# gdo_v7.net
KiCad netlist of a schematic drawn in EAGLE
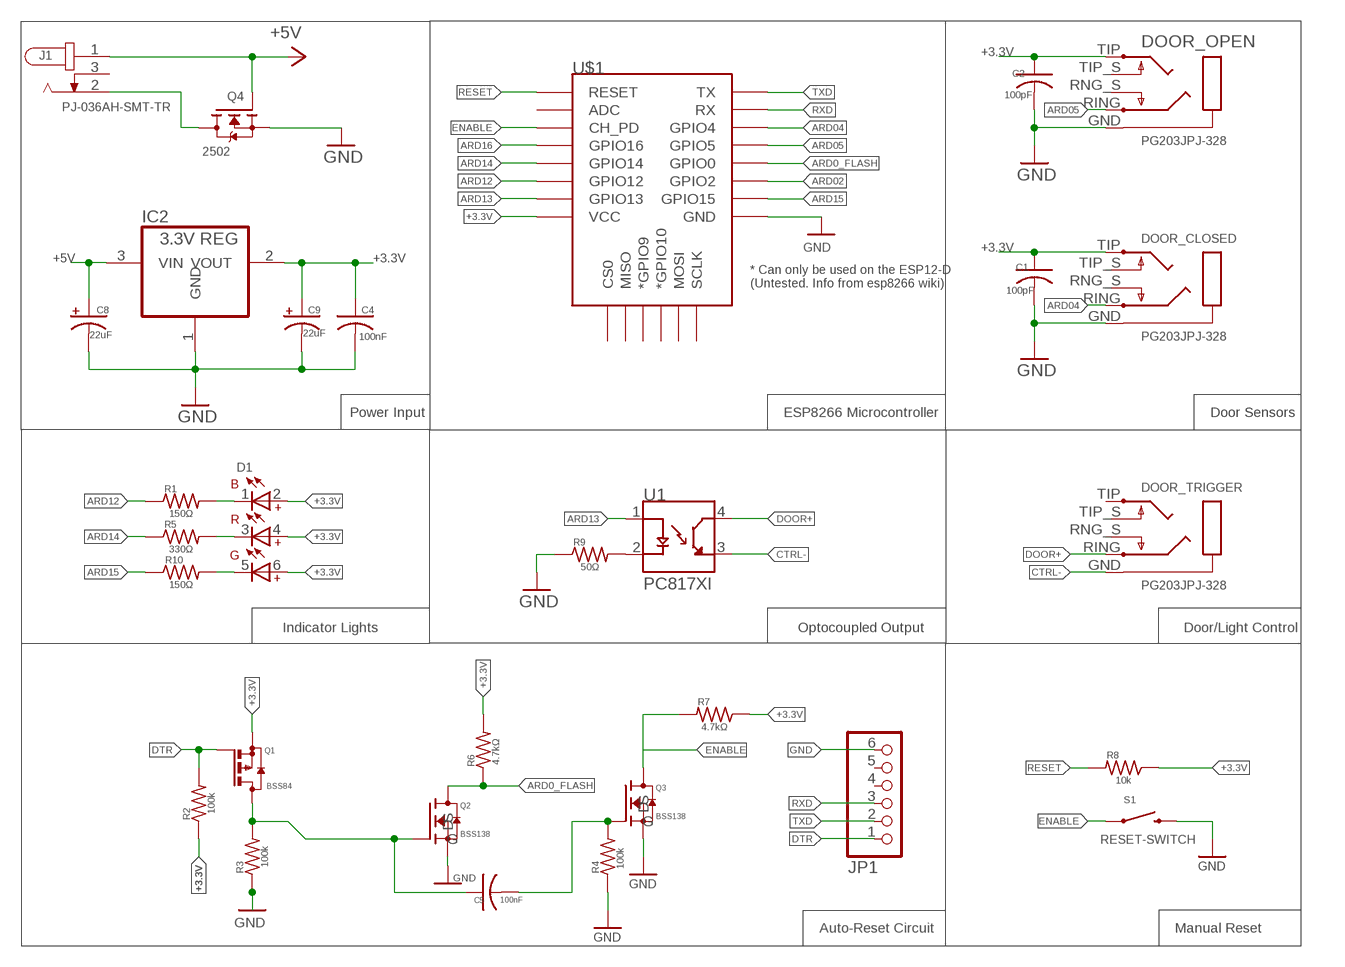
[diagram p0: schematic, sheet 1]

(export (version "E")
  (design (tool "Eeschema 10.0.6"))
  (components
    (comp (ref "C1")
      (value "100pF")
      (footprint "eagle-import:C0805")
      (libsource (lib "eagle-import") (part "C-USC0805"))
    )
    (comp (ref "C2")
      (value "100pF")
      (footprint "eagle-import:C0805")
      (libsource (lib "eagle-import") (part "C-USC0805"))
    )
    (comp (ref "C4")
      (value "100nF")
      (footprint "eagle-import:C0805")
      (libsource (lib "eagle-import") (part "C-USC0805"))
    )
    (comp (ref "C5")
      (value "100nF")
      (footprint "eagle-import:C0805")
      (libsource (lib "eagle-import") (part "C-USC0805"))
    )
    (comp (ref "C8")
      (value "22uF")
      (footprint "eagle-import:EIA3216")
      (libsource (lib "eagle-import") (part "10UF-TANT"))
    )
    (comp (ref "C9")
      (value "22uF")
      (footprint "eagle-import:EIA3216")
      (libsource (lib "eagle-import") (part "10UF-TANT"))
    )
    (comp (ref "D1")
      (value "WL-SFTW_5050_PLCC6_150505M173300")
      (footprint "eagle-import:WL-SFTW_5050_PLCC6")
      (libsource (lib "eagle-import") (part "WL-SFTW_5050_PLCC6_150505M173300"))
    )
    (comp (ref "DOOR_CLOSED")
      (value "PG203JPJ-328")
      (footprint "eagle-import:PG203J")
      (libsource (lib "eagle-import") (part "PG203JPJ-328"))
    )
    (comp (ref "DOOR_OPEN")
      (value "PG203JPJ-328")
      (footprint "eagle-import:PG203J")
      (libsource (lib "eagle-import") (part "PG203JPJ-328"))
    )
    (comp (ref "DOOR_TRIGGER")
      (value "PG203JPJ-328")
      (footprint "eagle-import:PG203J")
      (libsource (lib "eagle-import") (part "PG203JPJ-328"))
    )
    (comp (ref "IC2")
      (value "3.3V REG")
      (footprint "eagle-import:SOT223")
      (fields (field (name "MPN") "REG1117"))
      (libsource (lib "eagle-import") (part "REG1117"))
    )
    (comp (ref "J1")
      (value "PJ-036AH-SMT-TR")
      (footprint "eagle-import:CUI_PJ-036AH-SMT-TR")
      (fields (field (name "MF") "CUI Devices"))
      (libsource (lib "eagle-import") (part "PJ-036AH-SMT-TR"))
    )
    (comp (ref "JP1")
      (value "PINHD-1X6")
      (footprint "eagle-import:1X06")
      (libsource (lib "eagle-import") (part "PINHD-1X6"))
    )
    (comp (ref "Q1")
      (value "BSS84")
      (footprint "eagle-import:SOT23")
      (libsource (lib "eagle-import") (part "BSS84"))
    )
    (comp (ref "Q2")
      (value "BSS138")
      (footprint "eagle-import:BSS138")
      (libsource (lib "eagle-import") (part "BSS138"))
    )
    (comp (ref "Q3")
      (value "BSS138")
      (footprint "eagle-import:BSS138")
      (libsource (lib "eagle-import") (part "BSS138"))
    )
    (comp (ref "Q4")
      (value "2502")
      (footprint "eagle-import:SOT23")
      (fields (field (name "MF") "Fairchild") (field (name "MPN") "BSS138"))
      (libsource (lib "eagle-import") (part "bss138_10_BSS138"))
    )
    (comp (ref "R1")
      (value "150Ω")
      (footprint "eagle-import:R0805")
      (libsource (lib "eagle-import") (part "R-US_R0805"))
    )
    (comp (ref "R2")
      (value "100k")
      (footprint "eagle-import:R0805")
      (libsource (lib "eagle-import") (part "R-US_R0805"))
    )
    (comp (ref "R3")
      (value "100k")
      (footprint "eagle-import:R0805")
      (libsource (lib "eagle-import") (part "R-US_R0805"))
    )
    (comp (ref "R4")
      (value "100k")
      (footprint "eagle-import:R0805")
      (libsource (lib "eagle-import") (part "R-US_R0805"))
    )
    (comp (ref "R5")
      (value "330Ω")
      (footprint "eagle-import:R0805")
      (libsource (lib "eagle-import") (part "R-US_R0805"))
    )
    (comp (ref "R6")
      (value "4.7kΩ")
      (footprint "eagle-import:R0805")
      (libsource (lib "eagle-import") (part "R-US_R0805"))
    )
    (comp (ref "R7")
      (value "4.7kΩ")
      (footprint "eagle-import:R0805")
      (libsource (lib "eagle-import") (part "R-US_R0805"))
    )
    (comp (ref "R8")
      (value "10k")
      (footprint "eagle-import:R0805")
      (libsource (lib "eagle-import") (part "R-US_R0805"))
    )
    (comp (ref "R9")
      (value "50Ω")
      (footprint "eagle-import:R0805")
      (libsource (lib "eagle-import") (part "R-US_R0805"))
    )
    (comp (ref "R10")
      (value "150Ω")
      (footprint "eagle-import:R0805")
      (libsource (lib "eagle-import") (part "R-US_R0805"))
    )
    (comp (ref "S1")
      (value "RESET-SWITCH")
      (footprint "eagle-import:TACTILE-SWITCH-1101NE")
      (libsource (lib "eagle-import") (part "SWITCH-MOMENTARY-2-SMD-1101NE"))
    )
    (comp (ref "U$1")
      (value "ESP12ESMD")
      (footprint "eagle-import:ESP12E-SMD")
      (libsource (lib "eagle-import") (part "ESP12ESMD"))
    )
    (comp (ref "U1")
      (value "PC817XI")
      (footprint "eagle-import:SOIC254P975X460-4N")
      (fields (field (name "MF") "Sharp Microelectronics"))
      (libsource (lib "eagle-import") (part "PC817XI"))
    )
  )
  (nets
    (net (code "1") (name "+3.3V") (class "Default")
      (node (ref "C1") (pin "1") (pinfunction "1_1") (pintype "passive"))
      (node (ref "C2") (pin "1") (pinfunction "1_1") (pintype "passive"))
      (node (ref "C4") (pin "1") (pinfunction "1_1") (pintype "passive"))
      (node (ref "C9") (pin "A") (pinfunction "+_A") (pintype "passive"))
      (node (ref "D1") (pin "2") (pinfunction "2_2") (pintype "passive"))
      (node (ref "D1") (pin "4") (pinfunction "4_4") (pintype "passive"))
      (node (ref "D1") (pin "6") (pinfunction "6_6") (pintype "passive"))
      (node (ref "DOOR_CLOSED") (pin "TIP") (pinfunction "5_TIP") (pintype "passive"))
      (node (ref "DOOR_OPEN") (pin "TIP") (pinfunction "5_TIP") (pintype "passive"))
      (node (ref "IC2") (pin "2") (pinfunction "VOUT_2") (pintype "output"))
      (node (ref "Q1") (pin "2") (pinfunction "S_2") (pintype "passive"))
      (node (ref "R2") (pin "1") (pinfunction "1_1") (pintype "passive"))
      (node (ref "R6") (pin "2") (pinfunction "2_2") (pintype "passive"))
      (node (ref "R7") (pin "1") (pinfunction "1_1") (pintype "passive"))
      (node (ref "R8") (pin "1") (pinfunction "1_1") (pintype "passive"))
      (node (ref "U$1") (pin "VCC") (pinfunction "VCC_VCC") (pintype "bidirectional"))
    )
    (net (code "2") (name "+5V") (class "Default")
      (node (ref "C8") (pin "A") (pinfunction "+_A") (pintype "passive"))
      (node (ref "IC2") (pin "3") (pinfunction "VIN_3") (pintype "input"))
      (node (ref "J1") (pin "1") (pinfunction "1_1") (pintype "passive"))
      (node (ref "Q4") (pin "1") (pinfunction "G_1") (pintype "passive"))
    )
    (net (code "3") (name "ARD0_FLASH") (class "Default")
      (node (ref "Q2") (pin "D") (pinfunction "D_D") (pintype "passive"))
      (node (ref "R6") (pin "1") (pinfunction "1_1") (pintype "passive"))
      (node (ref "U$1") (pin "GPIO0") (pinfunction "GPIO0_GPIO0") (pintype "bidirectional"))
    )
    (net (code "4") (name "ARD02") (class "Default")
      (node (ref "U$1") (pin "GPIO2") (pinfunction "GPIO2_GPIO2") (pintype "bidirectional"))
    )
    (net (code "5") (name "ARD04") (class "Default")
      (node (ref "DOOR_CLOSED") (pin "RING") (pinfunction "2_RING") (pintype "passive"))
      (node (ref "U$1") (pin "GPIO4") (pinfunction "GPIO4_GPIO4") (pintype "bidirectional"))
    )
    (net (code "6") (name "ARD05") (class "Default")
      (node (ref "DOOR_OPEN") (pin "RING") (pinfunction "2_RING") (pintype "passive"))
      (node (ref "U$1") (pin "GPIO5") (pinfunction "GPIO5_GPIO5") (pintype "bidirectional"))
    )
    (net (code "7") (name "ARD12") (class "Default")
      (node (ref "R1") (pin "1") (pinfunction "1_1") (pintype "passive"))
      (node (ref "U$1") (pin "GPIO12") (pinfunction "GPIO12_GPIO12") (pintype "bidirectional"))
    )
    (net (code "8") (name "ARD13") (class "Default")
      (node (ref "U$1") (pin "GPIO13") (pinfunction "GPIO13_GPIO13") (pintype "bidirectional"))
      (node (ref "U1") (pin "1") (pinfunction "A_1") (pintype "passive"))
    )
    (net (code "9") (name "ARD14") (class "Default")
      (node (ref "R5") (pin "1") (pinfunction "1_1") (pintype "passive"))
      (node (ref "U$1") (pin "GPIO14") (pinfunction "GPIO14_GPIO14") (pintype "bidirectional"))
    )
    (net (code "10") (name "ARD15") (class "Default")
      (node (ref "R10") (pin "1") (pinfunction "1_1") (pintype "passive"))
      (node (ref "U$1") (pin "GPIO15") (pinfunction "GPIO15_GPIO15") (pintype "bidirectional"))
    )
    (net (code "11") (name "ARD16") (class "Default")
      (node (ref "U$1") (pin "GPIO16") (pinfunction "GPIO16_GPIO16") (pintype "bidirectional"))
    )
    (net (code "12") (name "CTRL-") (class "Default")
      (node (ref "DOOR_TRIGGER") (pin "GND") (pinfunction "1_GND") (pintype "passive"))
      (node (ref "U1") (pin "3") (pinfunction "ET_3") (pintype "passive"))
    )
    (net (code "13") (name "DOOR+") (class "Default")
      (node (ref "DOOR_TRIGGER") (pin "RING") (pinfunction "2_RING") (pintype "passive"))
      (node (ref "U1") (pin "4") (pinfunction "CT_4") (pintype "passive"))
    )
    (net (code "14") (name "DTR") (class "Default")
      (node (ref "JP1") (pin "1") (pinfunction "1_1") (pintype "passive"))
      (node (ref "Q1") (pin "1") (pinfunction "G_1") (pintype "passive"))
      (node (ref "R2") (pin "2") (pinfunction "2_2") (pintype "passive"))
    )
    (net (code "15") (name "ENABLE") (class "Default")
      (node (ref "Q3") (pin "D") (pinfunction "D_D") (pintype "passive"))
      (node (ref "R7") (pin "2") (pinfunction "2_2") (pintype "passive"))
      (node (ref "S1") (pin "P$1") (pinfunction "1_P$1") (pintype "passive"))
      (node (ref "U$1") (pin "CH_PD") (pinfunction "CH_PD_CH_PD") (pintype "bidirectional"))
    )
    (net (code "16") (name "GND") (class "Default")
      (node (ref "C1") (pin "2") (pinfunction "2_2") (pintype "passive"))
      (node (ref "C2") (pin "2") (pinfunction "2_2") (pintype "passive"))
      (node (ref "C4") (pin "2") (pinfunction "2_2") (pintype "passive"))
      (node (ref "C8") (pin "C") (pinfunction "-_C") (pintype "passive"))
      (node (ref "C9") (pin "C") (pinfunction "-_C") (pintype "passive"))
      (node (ref "DOOR_CLOSED") (pin "GND") (pinfunction "1_GND") (pintype "passive"))
      (node (ref "DOOR_OPEN") (pin "GND") (pinfunction "1_GND") (pintype "passive"))
      (node (ref "IC2") (pin "1") (pinfunction "GND_1") (pintype "power_in"))
      (node (ref "JP1") (pin "6") (pinfunction "6_6") (pintype "passive"))
      (node (ref "Q2") (pin "S") (pinfunction "S_S") (pintype "passive"))
      (node (ref "Q3") (pin "S") (pinfunction "S_S") (pintype "passive"))
      (node (ref "Q4") (pin "2") (pinfunction "S_2") (pintype "passive"))
      (node (ref "R3") (pin "1") (pinfunction "1_1") (pintype "passive"))
      (node (ref "R4") (pin "1") (pinfunction "1_1") (pintype "passive"))
      (node (ref "R9") (pin "1") (pinfunction "1_1") (pintype "passive"))
      (node (ref "S1") (pin "P$2") (pinfunction "2_P$2") (pintype "passive"))
      (node (ref "U$1") (pin "GND") (pinfunction "GND_GND") (pintype "bidirectional"))
    )
    (net (code "17") (name "Net-(C5-Pad2)") (class "Default")
      (node (ref "C5") (pin "2") (pinfunction "2_2") (pintype "passive"))
      (node (ref "Q3") (pin "G") (pinfunction "G_G") (pintype "passive"))
      (node (ref "R4") (pin "2") (pinfunction "2_2") (pintype "passive"))
    )
    (net (code "18") (name "Net-(D1-Pad1)") (class "Default")
      (node (ref "D1") (pin "1") (pinfunction "1_1") (pintype "passive"))
      (node (ref "R1") (pin "2") (pinfunction "2_2") (pintype "passive"))
    )
    (net (code "19") (name "Net-(D1-Pad3)") (class "Default")
      (node (ref "D1") (pin "3") (pinfunction "3_3") (pintype "passive"))
      (node (ref "R5") (pin "2") (pinfunction "2_2") (pintype "passive"))
    )
    (net (code "20") (name "Net-(D1-Pad5)") (class "Default")
      (node (ref "D1") (pin "5") (pinfunction "5_5") (pintype "passive"))
      (node (ref "R10") (pin "2") (pinfunction "2_2") (pintype "passive"))
    )
    (net (code "21") (name "Net-(Q1-D)") (class "Default")
      (node (ref "C5") (pin "1") (pinfunction "1_1") (pintype "passive"))
      (node (ref "Q1") (pin "3") (pinfunction "D_3") (pintype "passive"))
      (node (ref "Q2") (pin "G") (pinfunction "G_G") (pintype "passive"))
      (node (ref "R3") (pin "2") (pinfunction "2_2") (pintype "passive"))
    )
    (net (code "22") (name "Net-(Q4-D)") (class "Default")
      (node (ref "J1") (pin "2") (pinfunction "2_2") (pintype "passive"))
      (node (ref "Q4") (pin "3") (pinfunction "D_3") (pintype "passive"))
    )
    (net (code "23") (name "Net-(U1-C)") (class "Default")
      (node (ref "R9") (pin "2") (pinfunction "2_2") (pintype "passive"))
      (node (ref "U1") (pin "2") (pinfunction "C_2") (pintype "passive"))
    )
    (net (code "24") (name "RESET") (class "Default")
      (node (ref "R8") (pin "2") (pinfunction "2_2") (pintype "passive"))
      (node (ref "U$1") (pin "RESET") (pinfunction "RESET_RESET") (pintype "bidirectional"))
    )
    (net (code "25") (name "RXD") (class "Default")
      (node (ref "JP1") (pin "3") (pinfunction "3_3") (pintype "passive"))
      (node (ref "U$1") (pin "RXD0") (pinfunction "RX_RXD0") (pintype "bidirectional"))
    )
    (net (code "26") (name "TXD") (class "Default")
      (node (ref "JP1") (pin "2") (pinfunction "2_2") (pintype "passive"))
      (node (ref "U$1") (pin "TXD0") (pinfunction "TX_TXD0") (pintype "bidirectional"))
    )
    (net (code "27") (name "unconnected-(DOOR_CLOSED-3-PadRNG_S)") (class "Default")
      (node (ref "DOOR_CLOSED") (pin "RNG_S") (pinfunction "3_RNG_S") (pintype "passive"))
    )
    (net (code "28") (name "unconnected-(DOOR_CLOSED-4-PadTIP_S)") (class "Default")
      (node (ref "DOOR_CLOSED") (pin "TIP_S") (pinfunction "4_TIP_S") (pintype "passive"))
    )
    (net (code "29") (name "unconnected-(DOOR_OPEN-3-PadRNG_S)") (class "Default")
      (node (ref "DOOR_OPEN") (pin "RNG_S") (pinfunction "3_RNG_S") (pintype "passive"))
    )
    (net (code "30") (name "unconnected-(DOOR_OPEN-4-PadTIP_S)") (class "Default")
      (node (ref "DOOR_OPEN") (pin "TIP_S") (pinfunction "4_TIP_S") (pintype "passive"))
    )
    (net (code "31") (name "unconnected-(DOOR_TRIGGER-3-PadRNG_S)") (class "Default")
      (node (ref "DOOR_TRIGGER") (pin "RNG_S") (pinfunction "3_RNG_S") (pintype "passive"))
    )
    (net (code "32") (name "unconnected-(DOOR_TRIGGER-4-PadTIP_S)") (class "Default")
      (node (ref "DOOR_TRIGGER") (pin "TIP_S") (pinfunction "4_TIP_S") (pintype "passive"))
    )
    (net (code "33") (name "unconnected-(DOOR_TRIGGER-5-PadTIP)") (class "Default")
      (node (ref "DOOR_TRIGGER") (pin "TIP") (pinfunction "5_TIP") (pintype "passive"))
    )
    (net (code "34") (name "unconnected-(J1-Pad3)") (class "Default")
      (node (ref "J1") (pin "3") (pinfunction "3_3") (pintype "passive"))
    )
    (net (code "35") (name "unconnected-(JP1-Pad4)") (class "Default")
      (node (ref "JP1") (pin "4") (pinfunction "4_4") (pintype "passive"))
    )
    (net (code "36") (name "unconnected-(JP1-Pad5)") (class "Default")
      (node (ref "JP1") (pin "5") (pinfunction "5_5") (pintype "passive"))
    )
    (net (code "37") (name "unconnected-(U$1-*GPIO9-PadGPIO9)") (class "Default")
      (node (ref "U$1") (pin "GPIO9") (pinfunction "*GPIO9_GPIO9") (pintype "bidirectional"))
    )
    (net (code "38") (name "unconnected-(U$1-*GPIO10-PadGPIO10)") (class "Default")
      (node (ref "U$1") (pin "GPIO10") (pinfunction "*GPIO10_GPIO10") (pintype "bidirectional"))
    )
    (net (code "39") (name "unconnected-(U$1-PadADC)") (class "Default")
      (node (ref "U$1") (pin "ADC") (pinfunction "ADC_ADC") (pintype "bidirectional"))
    )
    (net (code "40") (name "unconnected-(U$1-PadCS0)") (class "Default")
      (node (ref "U$1") (pin "CS0") (pinfunction "CS0_CS0") (pintype "bidirectional"))
    )
    (net (code "41") (name "unconnected-(U$1-PadMISO)") (class "Default")
      (node (ref "U$1") (pin "MISO") (pinfunction "MISO_MISO") (pintype "bidirectional"))
    )
    (net (code "42") (name "unconnected-(U$1-PadMOSI)") (class "Default")
      (node (ref "U$1") (pin "MOSI") (pinfunction "MOSI_MOSI") (pintype "bidirectional"))
    )
    (net (code "43") (name "unconnected-(U$1-PadSCLK)") (class "Default")
      (node (ref "U$1") (pin "SCLK") (pinfunction "SCLK_SCLK") (pintype "bidirectional"))
    )
  )
)
